# eCog120_VGA.net
KiCad netlist of a schematic drawn in EAGLE
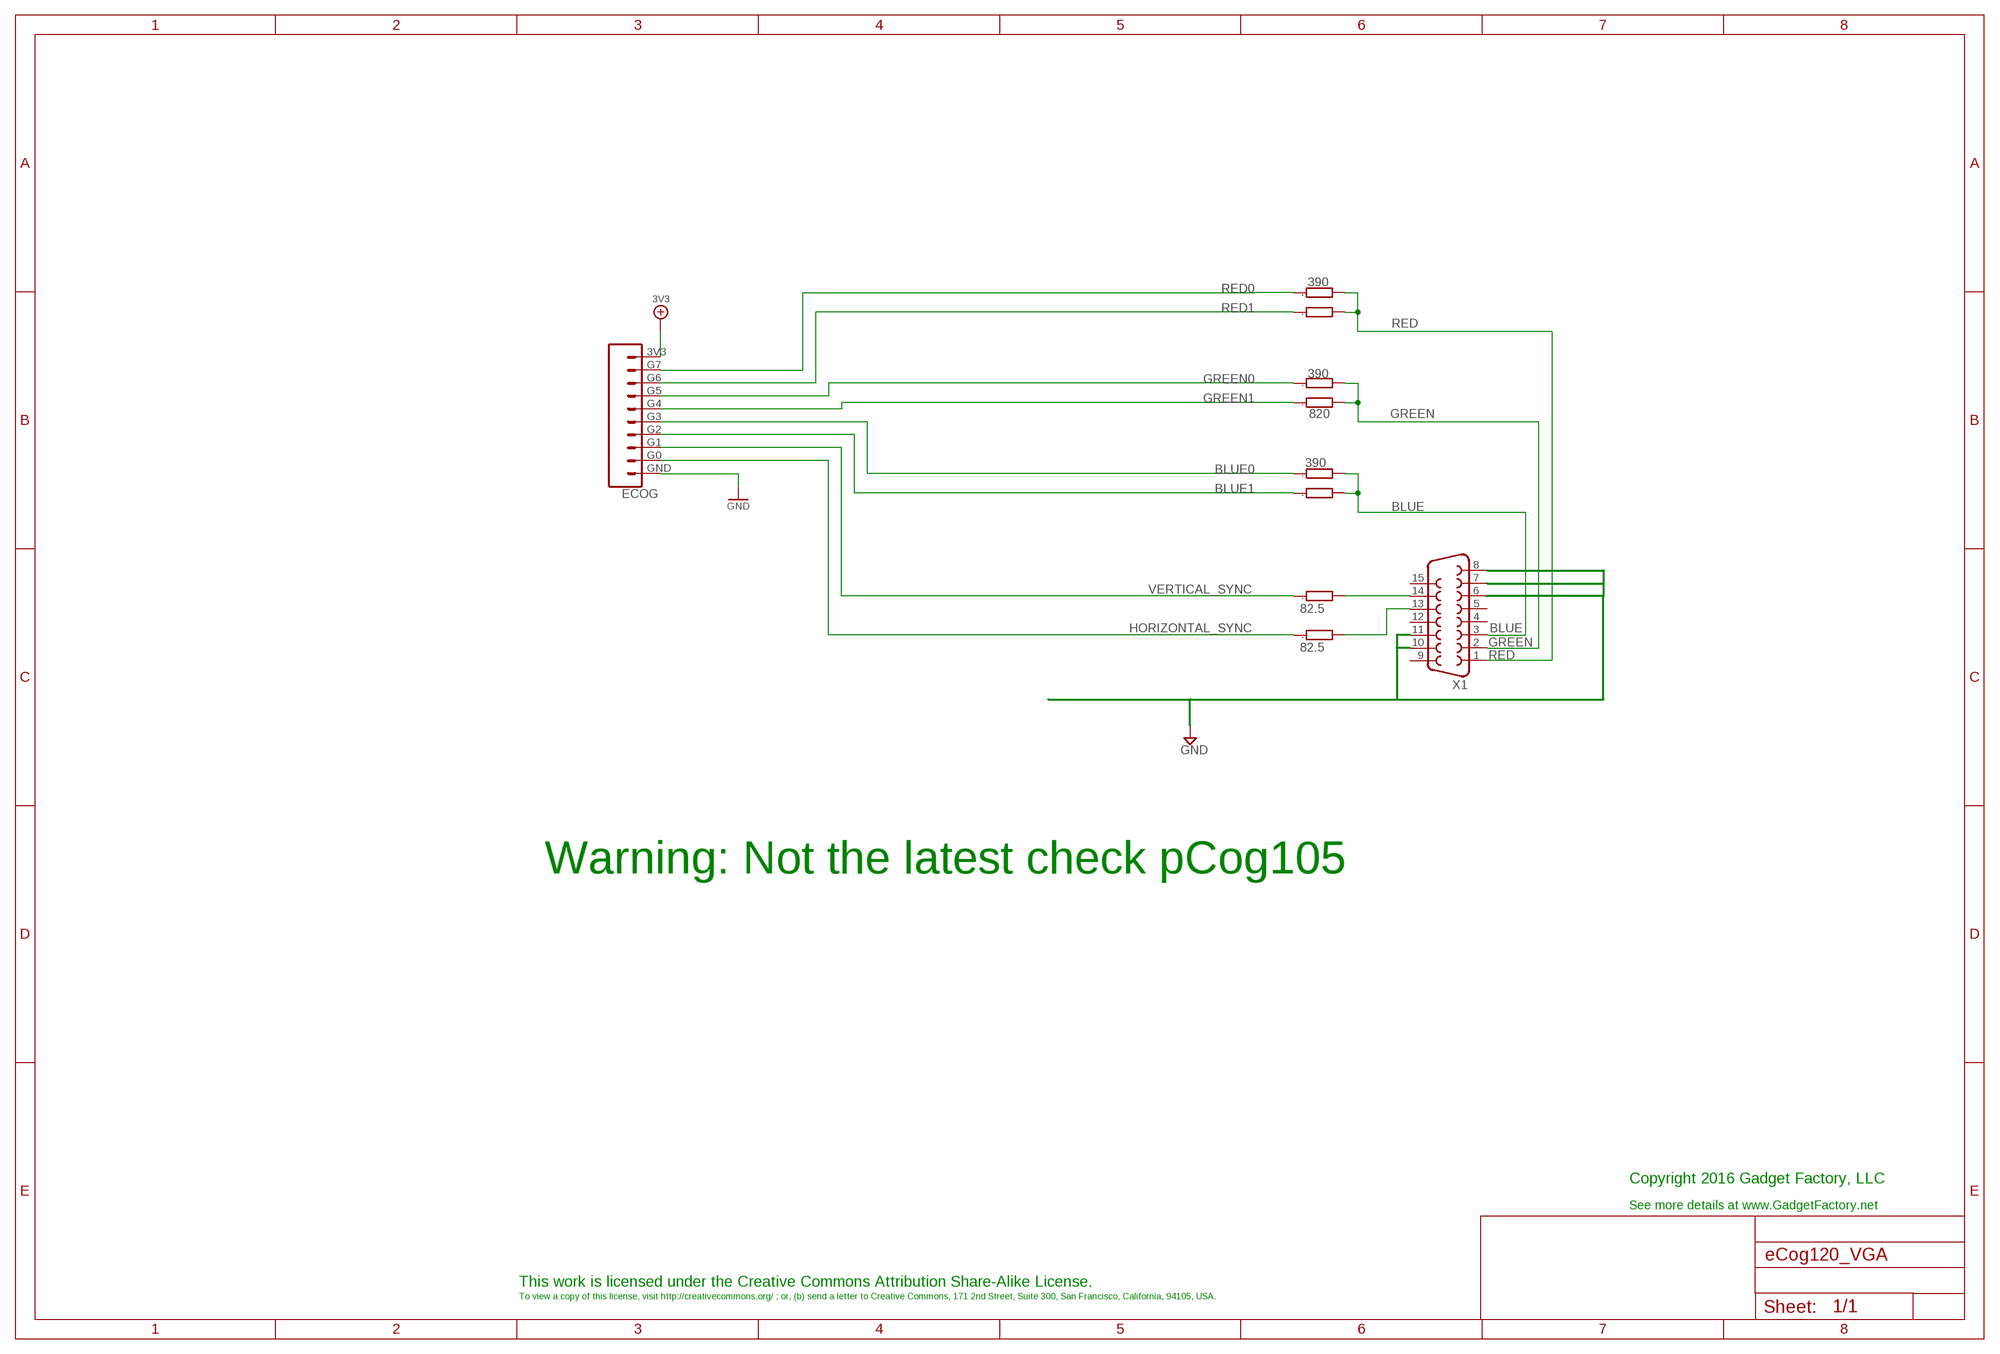
[diagram p0: schematic, sheet 1]

(export (version "E")
  (design (tool "Eeschema 10.0.6"))
  (components
    (comp (ref "ECOG")
      (value "ECOG_GENERAL_ROWTHROUGHOLE")
      (footprint "eagle-import:ECOG_GENERAL_TH")
      (libsource (lib "eagle-import") (part "ECOG_GENERAL_ROWTHROUGHOLE"))
    )
    (comp (ref "R34")
      (value "390")
      (footprint "eagle-import:0603")
      (fields (field (name "PARTNO") "RMCF0603JT3K90"))
      (libsource (lib "eagle-import") (part "R0603"))
    )
    (comp (ref "R35")
      (value "820")
      (footprint "eagle-import:0603")
      (fields (field (name "PARTNO") "RMCF0603JT2K00"))
      (libsource (lib "eagle-import") (part "R0603"))
    )
    (comp (ref "R40")
      (value "820")
      (footprint "eagle-import:0603")
      (fields (field (name "PARTNO") "RMCF0603JT2K00"))
      (libsource (lib "eagle-import") (part "R0603"))
    )
    (comp (ref "R41")
      (value "390")
      (footprint "eagle-import:0603")
      (fields (field (name "PARTNO") "RMCF0603JT3K90"))
      (libsource (lib "eagle-import") (part "R0603"))
    )
    (comp (ref "R44")
      (value "820")
      (footprint "eagle-import:0603")
      (fields (field (name "PARTNO") "RMCF0603JT2K00"))
      (libsource (lib "eagle-import") (part "R0603"))
    )
    (comp (ref "R45")
      (value "390")
      (footprint "eagle-import:0603")
      (fields (field (name "PARTNO") "RMCF0603JT3K90"))
      (libsource (lib "eagle-import") (part "R0603"))
    )
    (comp (ref "R46")
      (value "82.5")
      (footprint "eagle-import:0603")
      (fields (field (name "PARTNO") "RMCF0603FT82R5"))
      (libsource (lib "eagle-import") (part "R0603"))
    )
    (comp (ref "R47")
      (value "82.5")
      (footprint "eagle-import:0603")
      (fields (field (name "PARTNO") "RMCF0603FT82R5"))
      (libsource (lib "eagle-import") (part "R0603"))
    )
    (comp (ref "X1")
      (value "F15HDH")
      (footprint "eagle-import:HDF15H")
      (fields (field (name "PARTNO") "1-1734530-1"))
      (libsource (lib "eagle-import") (part "F15HDH"))
    )
  )
  (nets
    (net (code "1") (name "/BLUE") (class "Default")
      (node (ref "R44") (pin "2") (pinfunction "2_2") (pintype "passive"))
      (node (ref "R45") (pin "2") (pinfunction "2_2") (pintype "passive"))
      (node (ref "X1") (pin "3") (pinfunction "3_3") (pintype "passive"))
    )
    (net (code "2") (name "/BLUE0") (class "Default")
      (node (ref "ECOG") (pin "G3") (pinfunction "G3_G3") (pintype "passive"))
      (node (ref "R45") (pin "1") (pinfunction "1_1") (pintype "passive"))
    )
    (net (code "3") (name "/BLUE1") (class "Default")
      (node (ref "ECOG") (pin "G2") (pinfunction "G2_G2") (pintype "passive"))
      (node (ref "R44") (pin "1") (pinfunction "1_1") (pintype "passive"))
    )
    (net (code "4") (name "/GREEN") (class "Default")
      (node (ref "R40") (pin "2") (pinfunction "2_2") (pintype "passive"))
      (node (ref "R41") (pin "2") (pinfunction "2_2") (pintype "passive"))
      (node (ref "X1") (pin "2") (pinfunction "2_2") (pintype "passive"))
    )
    (net (code "5") (name "/GREEN0") (class "Default")
      (node (ref "ECOG") (pin "G5") (pinfunction "G5_G5") (pintype "passive"))
      (node (ref "R41") (pin "1") (pinfunction "1_1") (pintype "passive"))
    )
    (net (code "6") (name "/GREEN1") (class "Default")
      (node (ref "ECOG") (pin "G4") (pinfunction "G4_G4") (pintype "passive"))
      (node (ref "R40") (pin "1") (pinfunction "1_1") (pintype "passive"))
    )
    (net (code "7") (name "/HORIZONTAL_SYNC") (class "Default")
      (node (ref "ECOG") (pin "G0") (pinfunction "G0_G0") (pintype "passive"))
      (node (ref "R47") (pin "1") (pinfunction "1_1") (pintype "passive"))
    )
    (net (code "8") (name "/RED") (class "Default")
      (node (ref "R34") (pin "2") (pinfunction "2_2") (pintype "passive"))
      (node (ref "R35") (pin "2") (pinfunction "2_2") (pintype "passive"))
      (node (ref "X1") (pin "1") (pinfunction "1_1") (pintype "passive"))
    )
    (net (code "9") (name "/RED0") (class "Default")
      (node (ref "ECOG") (pin "G7") (pinfunction "G7_G7") (pintype "passive"))
      (node (ref "R34") (pin "1") (pinfunction "1_1") (pintype "passive"))
    )
    (net (code "10") (name "/RED1") (class "Default")
      (node (ref "ECOG") (pin "G6") (pinfunction "G6_G6") (pintype "passive"))
      (node (ref "R35") (pin "1") (pinfunction "1_1") (pintype "passive"))
    )
    (net (code "11") (name "/VERTICAL_SYNC") (class "Default")
      (node (ref "ECOG") (pin "G1") (pinfunction "G1_G1") (pintype "passive"))
      (node (ref "R46") (pin "1") (pinfunction "1_1") (pintype "passive"))
    )
    (net (code "12") (name "3V3") (class "Default")
      (node (ref "ECOG") (pin "3V3") (pinfunction "3V3_3V3") (pintype "power_in"))
    )
    (net (code "13") (name "GND") (class "Default")
      (node (ref "ECOG") (pin "GND") (pinfunction "GND_GND") (pintype "power_in"))
      (node (ref "X1") (pin "10") (pinfunction "10_10") (pintype "passive"))
      (node (ref "X1") (pin "11") (pinfunction "11_11") (pintype "passive"))
      (node (ref "X1") (pin "6") (pinfunction "6_6") (pintype "passive"))
      (node (ref "X1") (pin "7") (pinfunction "7_7") (pintype "passive"))
      (node (ref "X1") (pin "8") (pinfunction "8_8") (pintype "passive"))
    )
    (net (code "14") (name "Net-(R46-Pad2)") (class "Default")
      (node (ref "R46") (pin "2") (pinfunction "2_2") (pintype "passive"))
      (node (ref "X1") (pin "14") (pinfunction "14_14") (pintype "passive"))
    )
    (net (code "15") (name "Net-(R47-Pad2)") (class "Default")
      (node (ref "R47") (pin "2") (pinfunction "2_2") (pintype "passive"))
      (node (ref "X1") (pin "13") (pinfunction "13_13") (pintype "passive"))
    )
    (net (code "16") (name "unconnected-(X1-Pad4)") (class "Default")
      (node (ref "X1") (pin "4") (pinfunction "4_4") (pintype "passive"))
    )
    (net (code "17") (name "unconnected-(X1-Pad5)") (class "Default")
      (node (ref "X1") (pin "5") (pinfunction "5_5") (pintype "passive"))
    )
    (net (code "18") (name "unconnected-(X1-Pad9)") (class "Default")
      (node (ref "X1") (pin "9") (pinfunction "9_9") (pintype "passive"))
    )
    (net (code "19") (name "unconnected-(X1-Pad12)") (class "Default")
      (node (ref "X1") (pin "12") (pinfunction "12_12") (pintype "passive"))
    )
    (net (code "20") (name "unconnected-(X1-Pad15)") (class "Default")
      (node (ref "X1") (pin "15") (pinfunction "15_15") (pintype "passive"))
    )
  )
)
